# Button_Board.net
KiCad netlist of a schematic drawn in EAGLE
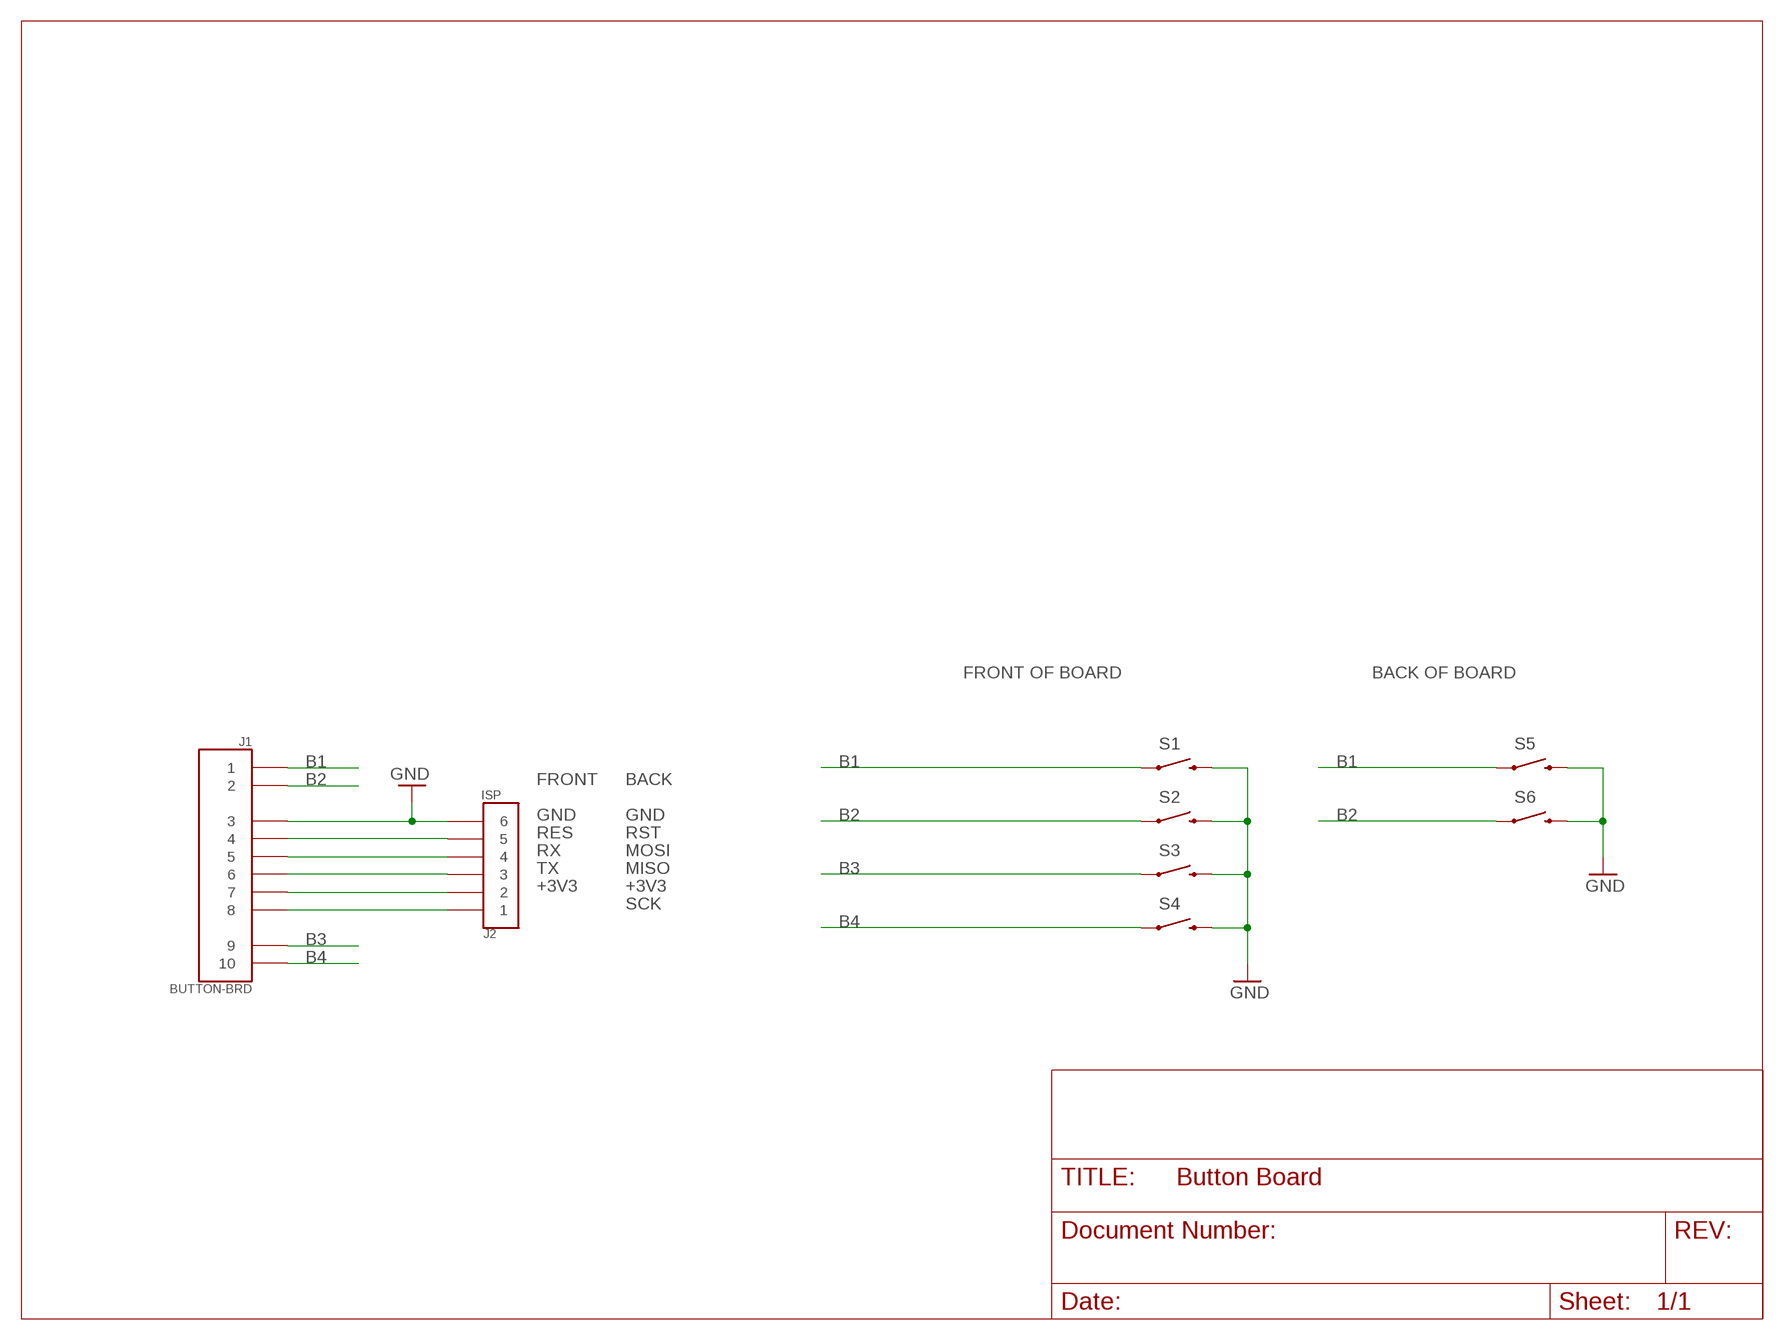
[diagram p0: schematic, sheet 1]

(export (version "E")
  (design (tool "Eeschema 10.0.6"))
  (components
    (comp (ref "J1")
      (value "BUTTON-BRD")
      (footprint "eagle-import:BUTTON-BRD")
      (libsource (lib "eagle-import") (part "BUTTON-BRD"))
    )
    (comp (ref "J2")
      (value "ISP")
      (footprint "eagle-import:ISP")
      (libsource (lib "eagle-import") (part "ISP"))
    )
    (comp (ref "S1")
      (value "TACT-SMD")
      (footprint "eagle-import:TACT-SMD")
      (libsource (lib "eagle-import") (part "TACT-SMD"))
    )
    (comp (ref "S2")
      (value "TACT-SMD")
      (footprint "eagle-import:TACT-SMD")
      (libsource (lib "eagle-import") (part "TACT-SMD"))
    )
    (comp (ref "S3")
      (value "TACT-SMD")
      (footprint "eagle-import:TACT-SMD")
      (libsource (lib "eagle-import") (part "TACT-SMD"))
    )
    (comp (ref "S4")
      (value "TACT-SMD")
      (footprint "eagle-import:TACT-SMD")
      (libsource (lib "eagle-import") (part "TACT-SMD"))
    )
    (comp (ref "S5")
      (value "TACT-SMD")
      (footprint "eagle-import:TACT-SMD")
      (libsource (lib "eagle-import") (part "TACT-SMD"))
    )
    (comp (ref "S6")
      (value "TACT-SMD")
      (footprint "eagle-import:TACT-SMD")
      (libsource (lib "eagle-import") (part "TACT-SMD"))
    )
  )
  (nets
    (net (code "1") (name "/B1") (class "Default")
      (node (ref "J1") (pin "1") (pinfunction "1_1") (pintype "bidirectional"))
      (node (ref "S1") (pin "P$1") (pinfunction "1_P$1") (pintype "passive"))
      (node (ref "S5") (pin "P$1") (pinfunction "1_P$1") (pintype "passive"))
    )
    (net (code "2") (name "/B2") (class "Default")
      (node (ref "J1") (pin "2") (pinfunction "2_2") (pintype "bidirectional"))
      (node (ref "S2") (pin "P$1") (pinfunction "1_P$1") (pintype "passive"))
      (node (ref "S6") (pin "P$1") (pinfunction "1_P$1") (pintype "passive"))
    )
    (net (code "3") (name "/B3") (class "Default")
      (node (ref "J1") (pin "9") (pinfunction "9_9") (pintype "bidirectional"))
      (node (ref "S3") (pin "P$1") (pinfunction "1_P$1") (pintype "passive"))
    )
    (net (code "4") (name "/B4") (class "Default")
      (node (ref "J1") (pin "10") (pinfunction "10_10") (pintype "bidirectional"))
      (node (ref "S4") (pin "P$1") (pinfunction "1_P$1") (pintype "passive"))
    )
    (net (code "5") (name "GND") (class "Default")
      (node (ref "J1") (pin "3") (pinfunction "3_3") (pintype "bidirectional"))
      (node (ref "J2") (pin "P$6") (pinfunction "6_P$6") (pintype "bidirectional"))
      (node (ref "S1") (pin "P$3") (pinfunction "2_P$3") (pintype "passive"))
      (node (ref "S2") (pin "P$3") (pinfunction "2_P$3") (pintype "passive"))
      (node (ref "S3") (pin "P$3") (pinfunction "2_P$3") (pintype "passive"))
      (node (ref "S4") (pin "P$3") (pinfunction "2_P$3") (pintype "passive"))
      (node (ref "S5") (pin "P$3") (pinfunction "2_P$3") (pintype "passive"))
      (node (ref "S6") (pin "P$3") (pinfunction "2_P$3") (pintype "passive"))
    )
    (net (code "6") (name "Net-(J2-1)") (class "Default")
      (node (ref "J1") (pin "8") (pinfunction "8_8") (pintype "bidirectional"))
      (node (ref "J2") (pin "P$1") (pinfunction "1_P$1") (pintype "bidirectional"))
    )
    (net (code "7") (name "Net-(J2-2)") (class "Default")
      (node (ref "J1") (pin "7") (pinfunction "7_7") (pintype "bidirectional"))
      (node (ref "J2") (pin "P$2") (pinfunction "2_P$2") (pintype "bidirectional"))
    )
    (net (code "8") (name "Net-(J2-3)") (class "Default")
      (node (ref "J1") (pin "6") (pinfunction "6_6") (pintype "bidirectional"))
      (node (ref "J2") (pin "P$3") (pinfunction "3_P$3") (pintype "bidirectional"))
    )
    (net (code "9") (name "Net-(J2-4)") (class "Default")
      (node (ref "J1") (pin "5") (pinfunction "5_5") (pintype "bidirectional"))
      (node (ref "J2") (pin "P$4") (pinfunction "4_P$4") (pintype "bidirectional"))
    )
    (net (code "10") (name "Net-(J2-5)") (class "Default")
      (node (ref "J1") (pin "4") (pinfunction "4_4") (pintype "bidirectional"))
      (node (ref "J2") (pin "P$5") (pinfunction "5_P$5") (pintype "bidirectional"))
    )
  )
)
